# LEDmatrixboard.net
KiCad netlist of a schematic drawn in EAGLE
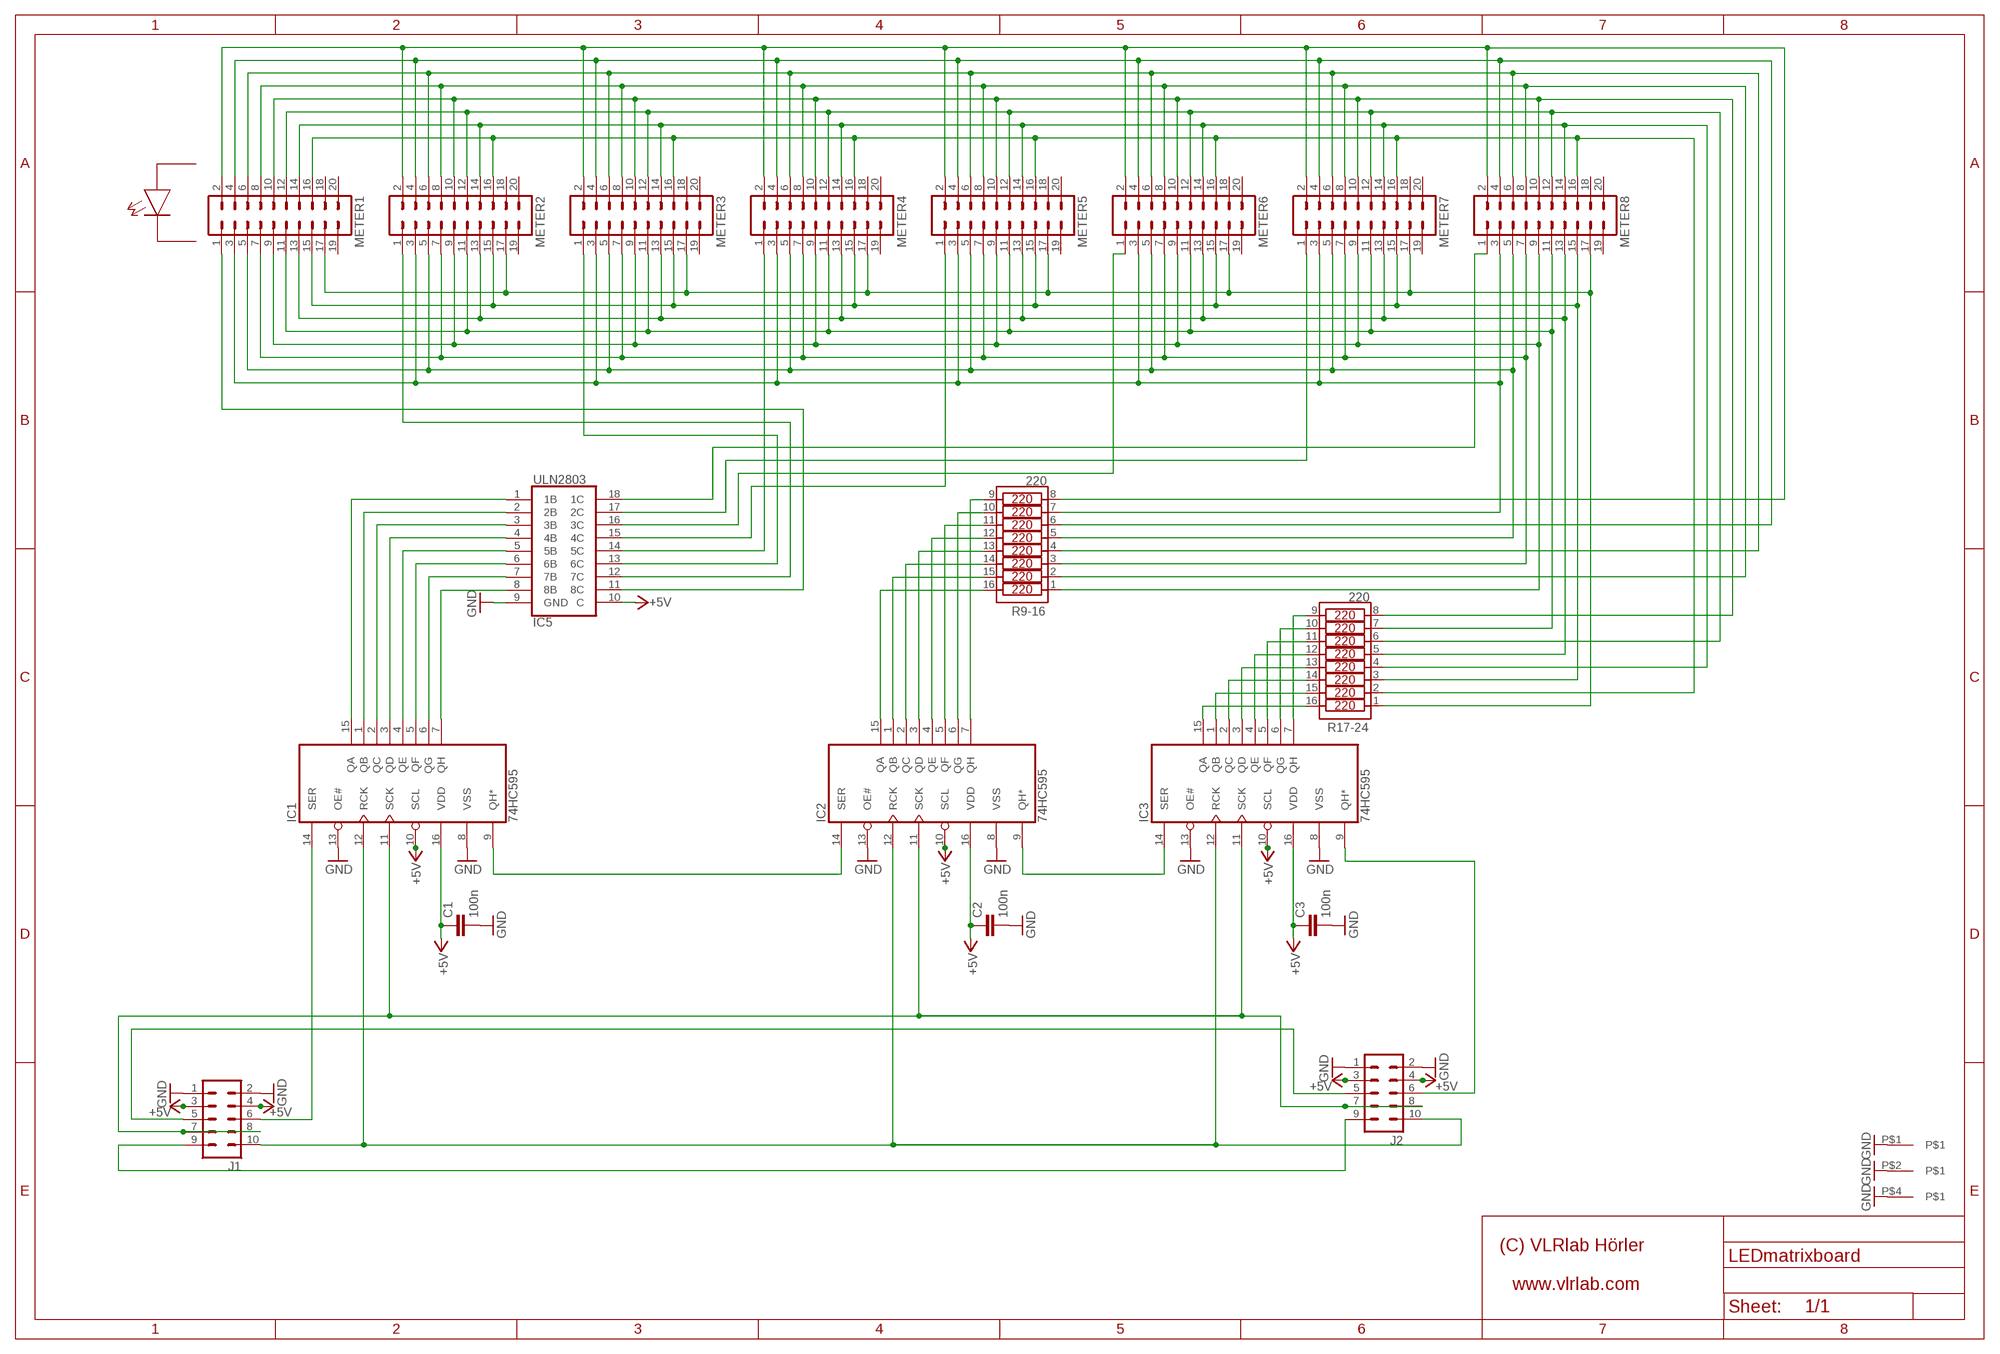
[diagram p0: schematic, sheet 1]

(export (version "E")
  (design (tool "Eeschema 10.0.6"))
  (components
    (comp (ref "C1")
      (value "100n")
      (footprint "eagle-import:C025-030X050")
      (libsource (lib "eagle-import") (part "C-EU025-030X050"))
    )
    (comp (ref "C2")
      (value "100n")
      (footprint "eagle-import:C025-030X050")
      (libsource (lib "eagle-import") (part "C-EU025-030X050"))
    )
    (comp (ref "C3")
      (value "100n")
      (footprint "eagle-import:C025-030X050")
      (libsource (lib "eagle-import") (part "C-EU025-030X050"))
    )
    (comp (ref "IC1")
      (value "74HC595")
      (footprint "eagle-import:SO16D")
      (libsource (lib "eagle-import") (part "595-541-165-uln2803_74HC595SO16D"))
    )
    (comp (ref "IC2")
      (value "74HC595")
      (footprint "eagle-import:SO16D")
      (libsource (lib "eagle-import") (part "595-541-165-uln2803_74HC595SO16D"))
    )
    (comp (ref "IC3")
      (value "74HC595")
      (footprint "eagle-import:SO16D")
      (libsource (lib "eagle-import") (part "595-541-165-uln2803_74HC595SO16D"))
    )
    (comp (ref "IC5")
      (value "ULN2803")
      (footprint "eagle-import:SO18W")
      (libsource (lib "eagle-import") (part "ULN2803SO18W"))
    )
    (comp (ref "J1")
      (value "ML10")
      (footprint "eagle-import:ML10")
      (libsource (lib "eagle-import") (part "ML10"))
    )
    (comp (ref "J2")
      (value "ML10")
      (footprint "eagle-import:ML10")
      (libsource (lib "eagle-import") (part "ML10"))
    )
    (comp (ref "METER1")
      (value "ML20")
      (footprint "eagle-import:ML20")
      (libsource (lib "eagle-import") (part "ML20"))
    )
    (comp (ref "METER2")
      (value "ML20")
      (footprint "eagle-import:ML20")
      (libsource (lib "eagle-import") (part "ML20"))
    )
    (comp (ref "METER3")
      (value "ML20")
      (footprint "eagle-import:ML20")
      (libsource (lib "eagle-import") (part "ML20"))
    )
    (comp (ref "METER4")
      (value "ML20")
      (footprint "eagle-import:ML20")
      (libsource (lib "eagle-import") (part "ML20"))
    )
    (comp (ref "METER5")
      (value "ML20")
      (footprint "eagle-import:ML20")
      (libsource (lib "eagle-import") (part "ML20"))
    )
    (comp (ref "METER6")
      (value "ML20")
      (footprint "eagle-import:ML20")
      (libsource (lib "eagle-import") (part "ML20"))
    )
    (comp (ref "METER7")
      (value "ML20")
      (footprint "eagle-import:ML20")
      (libsource (lib "eagle-import") (part "ML20"))
    )
    (comp (ref "METER8")
      (value "ML20")
      (footprint "eagle-import:ML20")
      (libsource (lib "eagle-import") (part "ML20"))
    )
    (comp (ref "R9-16")
      (value "220")
      (footprint "eagle-import:SOIC16W")
      (libsource (lib "eagle-import") (part "4816P-1SOIC16W"))
    )
    (comp (ref "R17-24")
      (value "220")
      (footprint "eagle-import:SOIC16W")
      (libsource (lib "eagle-import") (part "4816P-1SOIC16W"))
    )
    (comp (ref "U$2")
      (value "MIDIBOX_HALF")
      (footprint "eagle-import:MIDIBOX14X6")
      (libsource (lib "eagle-import") (part "MIDIBOX_HALF"))
    )
  )
  (nets
    (net (code "1") (name "+5V") (class "Default")
      (node (ref "C1") (pin "1") (pinfunction "1_1") (pintype "passive"))
      (node (ref "C2") (pin "1") (pinfunction "1_1") (pintype "passive"))
      (node (ref "C3") (pin "1") (pinfunction "1_1") (pintype "passive"))
      (node (ref "IC1") (pin "10") (pinfunction "SCL_10") (pintype "input"))
      (node (ref "IC1") (pin "16") (pinfunction "VDD_16") (pintype "power_in"))
      (node (ref "IC2") (pin "10") (pinfunction "SCL_10") (pintype "input"))
      (node (ref "IC2") (pin "16") (pinfunction "VDD_16") (pintype "power_in"))
      (node (ref "IC3") (pin "10") (pinfunction "SCL_10") (pintype "input"))
      (node (ref "IC3") (pin "16") (pinfunction "VDD_16") (pintype "power_in"))
      (node (ref "IC5") (pin "10") (pinfunction "C_10") (pintype "passive"))
      (node (ref "J1") (pin "3") (pinfunction "3_3") (pintype "passive"))
      (node (ref "J1") (pin "4") (pinfunction "4_4") (pintype "passive"))
      (node (ref "J2") (pin "3") (pinfunction "3_3") (pintype "passive"))
      (node (ref "J2") (pin "4") (pinfunction "4_4") (pintype "passive"))
    )
    (net (code "2") (name "GND") (class "Default")
      (node (ref "C1") (pin "2") (pinfunction "2_2") (pintype "passive"))
      (node (ref "C2") (pin "2") (pinfunction "2_2") (pintype "passive"))
      (node (ref "C3") (pin "2") (pinfunction "2_2") (pintype "passive"))
      (node (ref "IC1") (pin "13") (pinfunction "OE#_13") (pintype "input"))
      (node (ref "IC1") (pin "8") (pinfunction "VSS_8") (pintype "power_in"))
      (node (ref "IC2") (pin "13") (pinfunction "OE#_13") (pintype "input"))
      (node (ref "IC2") (pin "8") (pinfunction "VSS_8") (pintype "power_in"))
      (node (ref "IC3") (pin "13") (pinfunction "OE#_13") (pintype "input"))
      (node (ref "IC3") (pin "8") (pinfunction "VSS_8") (pintype "power_in"))
      (node (ref "IC5") (pin "9") (pinfunction "GND_9") (pintype "power_in"))
      (node (ref "J1") (pin "1") (pinfunction "1_1") (pintype "passive"))
      (node (ref "J1") (pin "2") (pinfunction "2_2") (pintype "passive"))
      (node (ref "J2") (pin "1") (pinfunction "1_1") (pintype "passive"))
      (node (ref "J2") (pin "2") (pinfunction "2_2") (pintype "passive"))
      (node (ref "U$2") (pin "P$1") (pinfunction "P$1_P$1") (pintype "bidirectional"))
      (node (ref "U$2") (pin "P$2") (pinfunction "P$1_P$2") (pintype "bidirectional"))
      (node (ref "U$2") (pin "P$4") (pinfunction "P$1_P$4") (pintype "bidirectional"))
    )
    (net (code "3") (name "Net-(IC1-QA)") (class "Default")
      (node (ref "IC1") (pin "15") (pinfunction "QA_15") (pintype "tri_state"))
      (node (ref "IC5") (pin "1") (pinfunction "1B_1") (pintype "input"))
    )
    (net (code "4") (name "Net-(IC1-QB)") (class "Default")
      (node (ref "IC1") (pin "1") (pinfunction "QB_1") (pintype "tri_state"))
      (node (ref "IC5") (pin "2") (pinfunction "2B_2") (pintype "input"))
    )
    (net (code "5") (name "Net-(IC1-QC)") (class "Default")
      (node (ref "IC1") (pin "2") (pinfunction "QC_2") (pintype "tri_state"))
      (node (ref "IC5") (pin "3") (pinfunction "3B_3") (pintype "input"))
    )
    (net (code "6") (name "Net-(IC1-QD)") (class "Default")
      (node (ref "IC1") (pin "3") (pinfunction "QD_3") (pintype "tri_state"))
      (node (ref "IC5") (pin "4") (pinfunction "4B_4") (pintype "input"))
    )
    (net (code "7") (name "Net-(IC1-QE)") (class "Default")
      (node (ref "IC1") (pin "4") (pinfunction "QE_4") (pintype "tri_state"))
      (node (ref "IC5") (pin "5") (pinfunction "5B_5") (pintype "input"))
    )
    (net (code "8") (name "Net-(IC1-QF)") (class "Default")
      (node (ref "IC1") (pin "5") (pinfunction "QF_5") (pintype "tri_state"))
      (node (ref "IC5") (pin "6") (pinfunction "6B_6") (pintype "input"))
    )
    (net (code "9") (name "Net-(IC1-QG)") (class "Default")
      (node (ref "IC1") (pin "6") (pinfunction "QG_6") (pintype "tri_state"))
      (node (ref "IC5") (pin "7") (pinfunction "7B_7") (pintype "input"))
    )
    (net (code "10") (name "Net-(IC1-QH)") (class "Default")
      (node (ref "IC1") (pin "7") (pinfunction "QH_7") (pintype "tri_state"))
      (node (ref "IC5") (pin "8") (pinfunction "8B_8") (pintype "input"))
    )
    (net (code "11") (name "Net-(IC1-QH*)") (class "Default")
      (node (ref "IC1") (pin "9") (pinfunction "QH*_9") (pintype "tri_state"))
      (node (ref "IC2") (pin "14") (pinfunction "SER_14") (pintype "input"))
    )
    (net (code "12") (name "Net-(IC1-RCK)") (class "Default")
      (node (ref "IC1") (pin "12") (pinfunction "RCK_12") (pintype "input"))
      (node (ref "IC2") (pin "12") (pinfunction "RCK_12") (pintype "input"))
      (node (ref "IC3") (pin "12") (pinfunction "RCK_12") (pintype "input"))
      (node (ref "J1") (pin "10") (pinfunction "10_10") (pintype "passive"))
      (node (ref "J2") (pin "10") (pinfunction "10_10") (pintype "passive"))
    )
    (net (code "13") (name "Net-(IC1-SCK)") (class "Default")
      (node (ref "IC1") (pin "11") (pinfunction "SCK_11") (pintype "input"))
      (node (ref "IC2") (pin "11") (pinfunction "SCK_11") (pintype "input"))
      (node (ref "IC3") (pin "11") (pinfunction "SCK_11") (pintype "input"))
      (node (ref "J1") (pin "7") (pinfunction "7_7") (pintype "passive"))
      (node (ref "J1") (pin "8") (pinfunction "8_8") (pintype "passive"))
      (node (ref "J2") (pin "7") (pinfunction "7_7") (pintype "passive"))
      (node (ref "J2") (pin "8") (pinfunction "8_8") (pintype "passive"))
    )
    (net (code "14") (name "Net-(IC1-SER)") (class "Default")
      (node (ref "IC1") (pin "14") (pinfunction "SER_14") (pintype "input"))
      (node (ref "J1") (pin "6") (pinfunction "6_6") (pintype "passive"))
    )
    (net (code "15") (name "Net-(IC2-QA)") (class "Default")
      (node (ref "IC2") (pin "15") (pinfunction "QA_15") (pintype "tri_state"))
      (node (ref "R9-16") (pin "16") (pinfunction "P$16_16") (pintype "passive"))
    )
    (net (code "16") (name "Net-(IC2-QB)") (class "Default")
      (node (ref "IC2") (pin "1") (pinfunction "QB_1") (pintype "tri_state"))
      (node (ref "R9-16") (pin "15") (pinfunction "P$15_15") (pintype "passive"))
    )
    (net (code "17") (name "Net-(IC2-QC)") (class "Default")
      (node (ref "IC2") (pin "2") (pinfunction "QC_2") (pintype "tri_state"))
      (node (ref "R9-16") (pin "14") (pinfunction "P$14_14") (pintype "passive"))
    )
    (net (code "18") (name "Net-(IC2-QD)") (class "Default")
      (node (ref "IC2") (pin "3") (pinfunction "QD_3") (pintype "tri_state"))
      (node (ref "R9-16") (pin "13") (pinfunction "P$13_13") (pintype "passive"))
    )
    (net (code "19") (name "Net-(IC2-QE)") (class "Default")
      (node (ref "IC2") (pin "4") (pinfunction "QE_4") (pintype "tri_state"))
      (node (ref "R9-16") (pin "12") (pinfunction "P$12_12") (pintype "passive"))
    )
    (net (code "20") (name "Net-(IC2-QF)") (class "Default")
      (node (ref "IC2") (pin "5") (pinfunction "QF_5") (pintype "tri_state"))
      (node (ref "R9-16") (pin "11") (pinfunction "P$11_11") (pintype "passive"))
    )
    (net (code "21") (name "Net-(IC2-QG)") (class "Default")
      (node (ref "IC2") (pin "6") (pinfunction "QG_6") (pintype "tri_state"))
      (node (ref "R9-16") (pin "10") (pinfunction "P$10_10") (pintype "passive"))
    )
    (net (code "22") (name "Net-(IC2-QH)") (class "Default")
      (node (ref "IC2") (pin "7") (pinfunction "QH_7") (pintype "tri_state"))
      (node (ref "R9-16") (pin "9") (pinfunction "P$9_9") (pintype "passive"))
    )
    (net (code "23") (name "Net-(IC2-QH*)") (class "Default")
      (node (ref "IC2") (pin "9") (pinfunction "QH*_9") (pintype "tri_state"))
      (node (ref "IC3") (pin "14") (pinfunction "SER_14") (pintype "input"))
    )
    (net (code "24") (name "Net-(IC3-QA)") (class "Default")
      (node (ref "IC3") (pin "15") (pinfunction "QA_15") (pintype "tri_state"))
      (node (ref "R17-24") (pin "16") (pinfunction "P$16_16") (pintype "passive"))
    )
    (net (code "25") (name "Net-(IC3-QB)") (class "Default")
      (node (ref "IC3") (pin "1") (pinfunction "QB_1") (pintype "tri_state"))
      (node (ref "R17-24") (pin "15") (pinfunction "P$15_15") (pintype "passive"))
    )
    (net (code "26") (name "Net-(IC3-QC)") (class "Default")
      (node (ref "IC3") (pin "2") (pinfunction "QC_2") (pintype "tri_state"))
      (node (ref "R17-24") (pin "14") (pinfunction "P$14_14") (pintype "passive"))
    )
    (net (code "27") (name "Net-(IC3-QD)") (class "Default")
      (node (ref "IC3") (pin "3") (pinfunction "QD_3") (pintype "tri_state"))
      (node (ref "R17-24") (pin "13") (pinfunction "P$13_13") (pintype "passive"))
    )
    (net (code "28") (name "Net-(IC3-QE)") (class "Default")
      (node (ref "IC3") (pin "4") (pinfunction "QE_4") (pintype "tri_state"))
      (node (ref "R17-24") (pin "12") (pinfunction "P$12_12") (pintype "passive"))
    )
    (net (code "29") (name "Net-(IC3-QF)") (class "Default")
      (node (ref "IC3") (pin "5") (pinfunction "QF_5") (pintype "tri_state"))
      (node (ref "R17-24") (pin "11") (pinfunction "P$11_11") (pintype "passive"))
    )
    (net (code "30") (name "Net-(IC3-QG)") (class "Default")
      (node (ref "IC3") (pin "6") (pinfunction "QG_6") (pintype "tri_state"))
      (node (ref "R17-24") (pin "10") (pinfunction "P$10_10") (pintype "passive"))
    )
    (net (code "31") (name "Net-(IC3-QH)") (class "Default")
      (node (ref "IC3") (pin "7") (pinfunction "QH_7") (pintype "tri_state"))
      (node (ref "R17-24") (pin "9") (pinfunction "P$9_9") (pintype "passive"))
    )
    (net (code "32") (name "Net-(IC3-QH*)") (class "Default")
      (node (ref "IC3") (pin "9") (pinfunction "QH*_9") (pintype "tri_state"))
      (node (ref "J2") (pin "6") (pinfunction "6_6") (pintype "passive"))
    )
    (net (code "33") (name "Net-(IC5-1C)") (class "Default")
      (node (ref "IC5") (pin "18") (pinfunction "1C_18") (pintype "open_collector"))
      (node (ref "METER8") (pin "1") (pinfunction "1_1") (pintype "passive"))
    )
    (net (code "34") (name "Net-(IC5-2C)") (class "Default")
      (node (ref "IC5") (pin "17") (pinfunction "2C_17") (pintype "open_collector"))
      (node (ref "METER7") (pin "1") (pinfunction "1_1") (pintype "passive"))
    )
    (net (code "35") (name "Net-(IC5-3C)") (class "Default")
      (node (ref "IC5") (pin "16") (pinfunction "3C_16") (pintype "open_collector"))
      (node (ref "METER6") (pin "1") (pinfunction "1_1") (pintype "passive"))
    )
    (net (code "36") (name "Net-(IC5-4C)") (class "Default")
      (node (ref "IC5") (pin "15") (pinfunction "4C_15") (pintype "open_collector"))
      (node (ref "METER5") (pin "1") (pinfunction "1_1") (pintype "passive"))
    )
    (net (code "37") (name "Net-(IC5-5C)") (class "Default")
      (node (ref "IC5") (pin "14") (pinfunction "5C_14") (pintype "open_collector"))
      (node (ref "METER4") (pin "1") (pinfunction "1_1") (pintype "passive"))
    )
    (net (code "38") (name "Net-(IC5-6C)") (class "Default")
      (node (ref "IC5") (pin "13") (pinfunction "6C_13") (pintype "open_collector"))
      (node (ref "METER3") (pin "1") (pinfunction "1_1") (pintype "passive"))
    )
    (net (code "39") (name "Net-(IC5-7C)") (class "Default")
      (node (ref "IC5") (pin "12") (pinfunction "7C_12") (pintype "open_collector"))
      (node (ref "METER2") (pin "1") (pinfunction "1_1") (pintype "passive"))
    )
    (net (code "40") (name "Net-(IC5-8C)") (class "Default")
      (node (ref "IC5") (pin "11") (pinfunction "8C_11") (pintype "open_collector"))
      (node (ref "METER1") (pin "1") (pinfunction "1_1") (pintype "passive"))
    )
    (net (code "41") (name "Net-(J1-Pad5)") (class "Default")
      (node (ref "J1") (pin "5") (pinfunction "5_5") (pintype "passive"))
      (node (ref "J2") (pin "5") (pinfunction "5_5") (pintype "passive"))
    )
    (net (code "42") (name "Net-(J1-Pad9)") (class "Default")
      (node (ref "J1") (pin "9") (pinfunction "9_9") (pintype "passive"))
      (node (ref "J2") (pin "9") (pinfunction "9_9") (pintype "passive"))
    )
    (net (code "43") (name "Net-(R9-16-P$1)") (class "Default")
      (node (ref "METER1") (pin "9") (pinfunction "9_9") (pintype "passive"))
      (node (ref "METER2") (pin "9") (pinfunction "9_9") (pintype "passive"))
      (node (ref "METER3") (pin "9") (pinfunction "9_9") (pintype "passive"))
      (node (ref "METER4") (pin "9") (pinfunction "9_9") (pintype "passive"))
      (node (ref "METER5") (pin "9") (pinfunction "9_9") (pintype "passive"))
      (node (ref "METER6") (pin "9") (pinfunction "9_9") (pintype "passive"))
      (node (ref "METER7") (pin "9") (pinfunction "9_9") (pintype "passive"))
      (node (ref "METER8") (pin "9") (pinfunction "9_9") (pintype "passive"))
      (node (ref "R9-16") (pin "1") (pinfunction "P$1_1") (pintype "passive"))
    )
    (net (code "44") (name "Net-(R9-16-P$2)") (class "Default")
      (node (ref "METER1") (pin "8") (pinfunction "8_8") (pintype "passive"))
      (node (ref "METER2") (pin "8") (pinfunction "8_8") (pintype "passive"))
      (node (ref "METER3") (pin "8") (pinfunction "8_8") (pintype "passive"))
      (node (ref "METER4") (pin "8") (pinfunction "8_8") (pintype "passive"))
      (node (ref "METER5") (pin "8") (pinfunction "8_8") (pintype "passive"))
      (node (ref "METER6") (pin "8") (pinfunction "8_8") (pintype "passive"))
      (node (ref "METER7") (pin "8") (pinfunction "8_8") (pintype "passive"))
      (node (ref "METER8") (pin "8") (pinfunction "8_8") (pintype "passive"))
      (node (ref "R9-16") (pin "2") (pinfunction "P$2_2") (pintype "passive"))
    )
    (net (code "45") (name "Net-(R9-16-P$3)") (class "Default")
      (node (ref "METER1") (pin "7") (pinfunction "7_7") (pintype "passive"))
      (node (ref "METER2") (pin "7") (pinfunction "7_7") (pintype "passive"))
      (node (ref "METER3") (pin "7") (pinfunction "7_7") (pintype "passive"))
      (node (ref "METER4") (pin "7") (pinfunction "7_7") (pintype "passive"))
      (node (ref "METER5") (pin "7") (pinfunction "7_7") (pintype "passive"))
      (node (ref "METER6") (pin "7") (pinfunction "7_7") (pintype "passive"))
      (node (ref "METER7") (pin "7") (pinfunction "7_7") (pintype "passive"))
      (node (ref "METER8") (pin "7") (pinfunction "7_7") (pintype "passive"))
      (node (ref "R9-16") (pin "3") (pinfunction "P$3_3") (pintype "passive"))
    )
    (net (code "46") (name "Net-(R9-16-P$4)") (class "Default")
      (node (ref "METER1") (pin "6") (pinfunction "6_6") (pintype "passive"))
      (node (ref "METER2") (pin "6") (pinfunction "6_6") (pintype "passive"))
      (node (ref "METER3") (pin "6") (pinfunction "6_6") (pintype "passive"))
      (node (ref "METER4") (pin "6") (pinfunction "6_6") (pintype "passive"))
      (node (ref "METER5") (pin "6") (pinfunction "6_6") (pintype "passive"))
      (node (ref "METER6") (pin "6") (pinfunction "6_6") (pintype "passive"))
      (node (ref "METER7") (pin "6") (pinfunction "6_6") (pintype "passive"))
      (node (ref "METER8") (pin "6") (pinfunction "6_6") (pintype "passive"))
      (node (ref "R9-16") (pin "4") (pinfunction "P$4_4") (pintype "passive"))
    )
    (net (code "47") (name "Net-(R9-16-P$5)") (class "Default")
      (node (ref "METER1") (pin "5") (pinfunction "5_5") (pintype "passive"))
      (node (ref "METER2") (pin "5") (pinfunction "5_5") (pintype "passive"))
      (node (ref "METER3") (pin "5") (pinfunction "5_5") (pintype "passive"))
      (node (ref "METER4") (pin "5") (pinfunction "5_5") (pintype "passive"))
      (node (ref "METER5") (pin "5") (pinfunction "5_5") (pintype "passive"))
      (node (ref "METER6") (pin "5") (pinfunction "5_5") (pintype "passive"))
      (node (ref "METER7") (pin "5") (pinfunction "5_5") (pintype "passive"))
      (node (ref "METER8") (pin "5") (pinfunction "5_5") (pintype "passive"))
      (node (ref "R9-16") (pin "5") (pinfunction "P$5_5") (pintype "passive"))
    )
    (net (code "48") (name "Net-(R9-16-P$6)") (class "Default")
      (node (ref "METER1") (pin "4") (pinfunction "4_4") (pintype "passive"))
      (node (ref "METER2") (pin "4") (pinfunction "4_4") (pintype "passive"))
      (node (ref "METER3") (pin "4") (pinfunction "4_4") (pintype "passive"))
      (node (ref "METER4") (pin "4") (pinfunction "4_4") (pintype "passive"))
      (node (ref "METER5") (pin "4") (pinfunction "4_4") (pintype "passive"))
      (node (ref "METER6") (pin "4") (pinfunction "4_4") (pintype "passive"))
      (node (ref "METER7") (pin "4") (pinfunction "4_4") (pintype "passive"))
      (node (ref "METER8") (pin "4") (pinfunction "4_4") (pintype "passive"))
      (node (ref "R9-16") (pin "6") (pinfunction "P$6_6") (pintype "passive"))
    )
    (net (code "49") (name "Net-(R9-16-P$7)") (class "Default")
      (node (ref "METER1") (pin "3") (pinfunction "3_3") (pintype "passive"))
      (node (ref "METER2") (pin "3") (pinfunction "3_3") (pintype "passive"))
      (node (ref "METER3") (pin "3") (pinfunction "3_3") (pintype "passive"))
      (node (ref "METER4") (pin "3") (pinfunction "3_3") (pintype "passive"))
      (node (ref "METER5") (pin "3") (pinfunction "3_3") (pintype "passive"))
      (node (ref "METER6") (pin "3") (pinfunction "3_3") (pintype "passive"))
      (node (ref "METER7") (pin "3") (pinfunction "3_3") (pintype "passive"))
      (node (ref "METER8") (pin "3") (pinfunction "3_3") (pintype "passive"))
      (node (ref "R9-16") (pin "7") (pinfunction "P$7_7") (pintype "passive"))
    )
    (net (code "50") (name "Net-(R9-16-P$8)") (class "Default")
      (node (ref "METER1") (pin "2") (pinfunction "2_2") (pintype "passive"))
      (node (ref "METER2") (pin "2") (pinfunction "2_2") (pintype "passive"))
      (node (ref "METER3") (pin "2") (pinfunction "2_2") (pintype "passive"))
      (node (ref "METER4") (pin "2") (pinfunction "2_2") (pintype "passive"))
      (node (ref "METER5") (pin "2") (pinfunction "2_2") (pintype "passive"))
      (node (ref "METER6") (pin "2") (pinfunction "2_2") (pintype "passive"))
      (node (ref "METER7") (pin "2") (pinfunction "2_2") (pintype "passive"))
      (node (ref "METER8") (pin "2") (pinfunction "2_2") (pintype "passive"))
      (node (ref "R9-16") (pin "8") (pinfunction "P$8_8") (pintype "passive"))
    )
    (net (code "51") (name "Net-(R17-24-P$1)") (class "Default")
      (node (ref "METER1") (pin "17") (pinfunction "17_17") (pintype "passive"))
      (node (ref "METER2") (pin "17") (pinfunction "17_17") (pintype "passive"))
      (node (ref "METER3") (pin "17") (pinfunction "17_17") (pintype "passive"))
      (node (ref "METER4") (pin "17") (pinfunction "17_17") (pintype "passive"))
      (node (ref "METER5") (pin "17") (pinfunction "17_17") (pintype "passive"))
      (node (ref "METER6") (pin "17") (pinfunction "17_17") (pintype "passive"))
      (node (ref "METER7") (pin "17") (pinfunction "17_17") (pintype "passive"))
      (node (ref "METER8") (pin "17") (pinfunction "17_17") (pintype "passive"))
      (node (ref "R17-24") (pin "1") (pinfunction "P$1_1") (pintype "passive"))
    )
    (net (code "52") (name "Net-(R17-24-P$2)") (class "Default")
      (node (ref "METER1") (pin "16") (pinfunction "16_16") (pintype "passive"))
      (node (ref "METER2") (pin "16") (pinfunction "16_16") (pintype "passive"))
      (node (ref "METER3") (pin "16") (pinfunction "16_16") (pintype "passive"))
      (node (ref "METER4") (pin "16") (pinfunction "16_16") (pintype "passive"))
      (node (ref "METER5") (pin "16") (pinfunction "16_16") (pintype "passive"))
      (node (ref "METER6") (pin "16") (pinfunction "16_16") (pintype "passive"))
      (node (ref "METER7") (pin "16") (pinfunction "16_16") (pintype "passive"))
      (node (ref "METER8") (pin "16") (pinfunction "16_16") (pintype "passive"))
      (node (ref "R17-24") (pin "2") (pinfunction "P$2_2") (pintype "passive"))
    )
    (net (code "53") (name "Net-(R17-24-P$3)") (class "Default")
      (node (ref "METER1") (pin "15") (pinfunction "15_15") (pintype "passive"))
      (node (ref "METER2") (pin "15") (pinfunction "15_15") (pintype "passive"))
      (node (ref "METER3") (pin "15") (pinfunction "15_15") (pintype "passive"))
      (node (ref "METER4") (pin "15") (pinfunction "15_15") (pintype "passive"))
      (node (ref "METER5") (pin "15") (pinfunction "15_15") (pintype "passive"))
      (node (ref "METER6") (pin "15") (pinfunction "15_15") (pintype "passive"))
      (node (ref "METER7") (pin "15") (pinfunction "15_15") (pintype "passive"))
      (node (ref "METER8") (pin "15") (pinfunction "15_15") (pintype "passive"))
      (node (ref "R17-24") (pin "3") (pinfunction "P$3_3") (pintype "passive"))
    )
    (net (code "54") (name "Net-(R17-24-P$4)") (class "Default")
      (node (ref "METER1") (pin "14") (pinfunction "14_14") (pintype "passive"))
      (node (ref "METER2") (pin "14") (pinfunction "14_14") (pintype "passive"))
      (node (ref "METER3") (pin "14") (pinfunction "14_14") (pintype "passive"))
      (node (ref "METER4") (pin "14") (pinfunction "14_14") (pintype "passive"))
      (node (ref "METER5") (pin "14") (pinfunction "14_14") (pintype "passive"))
      (node (ref "METER6") (pin "14") (pinfunction "14_14") (pintype "passive"))
      (node (ref "METER7") (pin "14") (pinfunction "14_14") (pintype "passive"))
      (node (ref "METER8") (pin "14") (pinfunction "14_14") (pintype "passive"))
      (node (ref "R17-24") (pin "4") (pinfunction "P$4_4") (pintype "passive"))
    )
    (net (code "55") (name "Net-(R17-24-P$5)") (class "Default")
      (node (ref "METER1") (pin "13") (pinfunction "13_13") (pintype "passive"))
      (node (ref "METER2") (pin "13") (pinfunction "13_13") (pintype "passive"))
      (node (ref "METER3") (pin "13") (pinfunction "13_13") (pintype "passive"))
      (node (ref "METER4") (pin "13") (pinfunction "13_13") (pintype "passive"))
      (node (ref "METER5") (pin "13") (pinfunction "13_13") (pintype "passive"))
      (node (ref "METER6") (pin "13") (pinfunction "13_13") (pintype "passive"))
      (node (ref "METER7") (pin "13") (pinfunction "13_13") (pintype "passive"))
      (node (ref "METER8") (pin "13") (pinfunction "13_13") (pintype "passive"))
      (node (ref "R17-24") (pin "5") (pinfunction "P$5_5") (pintype "passive"))
    )
    (net (code "56") (name "Net-(R17-24-P$6)") (class "Default")
      (node (ref "METER1") (pin "12") (pinfunction "12_12") (pintype "passive"))
      (node (ref "METER2") (pin "12") (pinfunction "12_12") (pintype "passive"))
      (node (ref "METER3") (pin "12") (pinfunction "12_12") (pintype "passive"))
      (node (ref "METER4") (pin "12") (pinfunction "12_12") (pintype "passive"))
      (node (ref "METER5") (pin "12") (pinfunction "12_12") (pintype "passive"))
      (node (ref "METER6") (pin "12") (pinfunction "12_12") (pintype "passive"))
      (node (ref "METER7") (pin "12") (pinfunction "12_12") (pintype "passive"))
      (node (ref "METER8") (pin "12") (pinfunction "12_12") (pintype "passive"))
      (node (ref "R17-24") (pin "6") (pinfunction "P$6_6") (pintype "passive"))
    )
    (net (code "57") (name "Net-(R17-24-P$7)") (class "Default")
      (node (ref "METER1") (pin "11") (pinfunction "11_11") (pintype "passive"))
      (node (ref "METER2") (pin "11") (pinfunction "11_11") (pintype "passive"))
      (node (ref "METER3") (pin "11") (pinfunction "11_11") (pintype "passive"))
      (node (ref "METER4") (pin "11") (pinfunction "11_11") (pintype "passive"))
      (node (ref "METER5") (pin "11") (pinfunction "11_11") (pintype "passive"))
      (node (ref "METER6") (pin "11") (pinfunction "11_11") (pintype "passive"))
      (node (ref "METER7") (pin "11") (pinfunction "11_11") (pintype "passive"))
      (node (ref "METER8") (pin "11") (pinfunction "11_11") (pintype "passive"))
      (node (ref "R17-24") (pin "7") (pinfunction "P$7_7") (pintype "passive"))
    )
    (net (code "58") (name "Net-(R17-24-P$8)") (class "Default")
      (node (ref "METER1") (pin "10") (pinfunction "10_10") (pintype "passive"))
      (node (ref "METER2") (pin "10") (pinfunction "10_10") (pintype "passive"))
      (node (ref "METER3") (pin "10") (pinfunction "10_10") (pintype "passive"))
      (node (ref "METER4") (pin "10") (pinfunction "10_10") (pintype "passive"))
      (node (ref "METER5") (pin "10") (pinfunction "10_10") (pintype "passive"))
      (node (ref "METER6") (pin "10") (pinfunction "10_10") (pintype "passive"))
      (node (ref "METER7") (pin "10") (pinfunction "10_10") (pintype "passive"))
      (node (ref "METER8") (pin "10") (pinfunction "10_10") (pintype "passive"))
      (node (ref "R17-24") (pin "8") (pinfunction "P$8_8") (pintype "passive"))
    )
    (net (code "59") (name "unconnected-(METER1-Pad18)") (class "Default")
      (node (ref "METER1") (pin "18") (pinfunction "18_18") (pintype "passive"))
    )
    (net (code "60") (name "unconnected-(METER1-Pad19)") (class "Default")
      (node (ref "METER1") (pin "19") (pinfunction "19_19") (pintype "passive"))
    )
    (net (code "61") (name "unconnected-(METER1-Pad20)") (class "Default")
      (node (ref "METER1") (pin "20") (pinfunction "20_20") (pintype "passive"))
    )
    (net (code "62") (name "unconnected-(METER2-Pad18)") (class "Default")
      (node (ref "METER2") (pin "18") (pinfunction "18_18") (pintype "passive"))
    )
    (net (code "63") (name "unconnected-(METER2-Pad19)") (class "Default")
      (node (ref "METER2") (pin "19") (pinfunction "19_19") (pintype "passive"))
    )
    (net (code "64") (name "unconnected-(METER2-Pad20)") (class "Default")
      (node (ref "METER2") (pin "20") (pinfunction "20_20") (pintype "passive"))
    )
    (net (code "65") (name "unconnected-(METER3-Pad18)") (class "Default")
      (node (ref "METER3") (pin "18") (pinfunction "18_18") (pintype "passive"))
    )
    (net (code "66") (name "unconnected-(METER3-Pad19)") (class "Default")
      (node (ref "METER3") (pin "19") (pinfunction "19_19") (pintype "passive"))
    )
    (net (code "67") (name "unconnected-(METER3-Pad20)") (class "Default")
      (node (ref "METER3") (pin "20") (pinfunction "20_20") (pintype "passive"))
    )
    (net (code "68") (name "unconnected-(METER4-Pad18)") (class "Default")
      (node (ref "METER4") (pin "18") (pinfunction "18_18") (pintype "passive"))
    )
    (net (code "69") (name "unconnected-(METER4-Pad19)") (class "Default")
      (node (ref "METER4") (pin "19") (pinfunction "19_19") (pintype "passive"))
    )
    (net (code "70") (name "unconnected-(METER4-Pad20)") (class "Default")
      (node (ref "METER4") (pin "20") (pinfunction "20_20") (pintype "passive"))
    )
    (net (code "71") (name "unconnected-(METER5-Pad18)") (class "Default")
      (node (ref "METER5") (pin "18") (pinfunction "18_18") (pintype "passive"))
    )
    (net (code "72") (name "unconnected-(METER5-Pad19)") (class "Default")
      (node (ref "METER5") (pin "19") (pinfunction "19_19") (pintype "passive"))
    )
    (net (code "73") (name "unconnected-(METER5-Pad20)") (class "Default")
      (node (ref "METER5") (pin "20") (pinfunction "20_20") (pintype "passive"))
    )
    (net (code "74") (name "unconnected-(METER6-Pad18)") (class "Default")
      (node (ref "METER6") (pin "18") (pinfunction "18_18") (pintype "passive"))
    )
    (net (code "75") (name "unconnected-(METER6-Pad19)") (class "Default")
      (node (ref "METER6") (pin "19") (pinfunction "19_19") (pintype "passive"))
    )
    (net (code "76") (name "unconnected-(METER6-Pad20)") (class "Default")
      (node (ref "METER6") (pin "20") (pinfunction "20_20") (pintype "passive"))
    )
    (net (code "77") (name "unconnected-(METER7-Pad18)") (class "Default")
      (node (ref "METER7") (pin "18") (pinfunction "18_18") (pintype "passive"))
    )
    (net (code "78") (name "unconnected-(METER7-Pad19)") (class "Default")
      (node (ref "METER7") (pin "19") (pinfunction "19_19") (pintype "passive"))
    )
    (net (code "79") (name "unconnected-(METER7-Pad20)") (class "Default")
      (node (ref "METER7") (pin "20") (pinfunction "20_20") (pintype "passive"))
    )
    (net (code "80") (name "unconnected-(METER8-Pad18)") (class "Default")
      (node (ref "METER8") (pin "18") (pinfunction "18_18") (pintype "passive"))
    )
    (net (code "81") (name "unconnected-(METER8-Pad19)") (class "Default")
      (node (ref "METER8") (pin "19") (pinfunction "19_19") (pintype "passive"))
    )
    (net (code "82") (name "unconnected-(METER8-Pad20)") (class "Default")
      (node (ref "METER8") (pin "20") (pinfunction "20_20") (pintype "passive"))
    )
  )
)
